# GPO_IF.net
KiCad netlist of a schematic drawn in Altium Designer
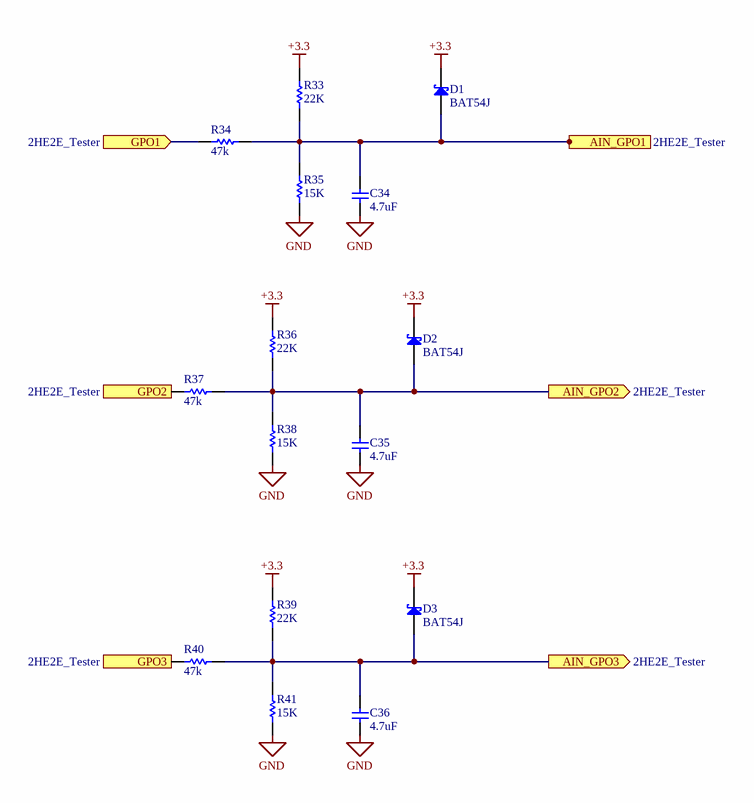
[diagram p0: GPO_IF.SchDoc]

(export (version "E")
  (design (tool "Eeschema 10.0.6"))
  (components
    (comp (ref "C34")
      (value "4.7uF")
      (footprint "0603M-C")
      (description "Ceramic Capacitor")
      (fields (field (name "Comment") "Cap Ceramic"))
      (libsource (lib "Plume") (part "Cap Ceramic"))
    )
    (comp (ref "C35")
      (value "4.7uF")
      (footprint "0603M-C")
      (description "Ceramic Capacitor")
      (fields (field (name "Comment") "Cap Ceramic"))
      (libsource (lib "Plume") (part "Cap Ceramic"))
    )
    (comp (ref "C36")
      (value "4.7uF")
      (footprint "0603M-C")
      (description "Ceramic Capacitor")
      (fields (field (name "Comment") "Cap Ceramic"))
      (libsource (lib "Plume") (part "Cap Ceramic"))
    )
    (comp (ref "D1")
      (value "BAT54J")
      (footprint "SOD323")
      (description "Diodo Schottky")
      (libsource (lib "Plume") (part "Diodo Schottky"))
    )
    (comp (ref "D2")
      (value "BAT54J")
      (footprint "SOD323")
      (description "Diodo Schottky")
      (libsource (lib "Plume") (part "Diodo Schottky"))
    )
    (comp (ref "D3")
      (value "BAT54J")
      (footprint "SOD323")
      (description "Diodo Schottky")
      (libsource (lib "Plume") (part "Diodo Schottky"))
    )
    (comp (ref "R33")
      (value "22K")
      (footprint "0603M")
      (description "Resistor")
      (libsource (lib "Plume") (part "Resistor"))
    )
    (comp (ref "R34")
      (value "47k")
      (footprint "0603M")
      (description "Resistor")
      (libsource (lib "Plume") (part "Resistor"))
    )
    (comp (ref "R35")
      (value "15K")
      (footprint "0603M")
      (description "Resistor")
      (libsource (lib "Plume") (part "Resistor"))
    )
    (comp (ref "R36")
      (value "22K")
      (footprint "0603M")
      (description "Resistor")
      (libsource (lib "Plume") (part "Resistor"))
    )
    (comp (ref "R37")
      (value "47k")
      (footprint "0603M")
      (description "Resistor")
      (libsource (lib "Plume") (part "Resistor"))
    )
    (comp (ref "R38")
      (value "15K")
      (footprint "0603M")
      (description "Resistor")
      (libsource (lib "Plume") (part "Resistor"))
    )
    (comp (ref "R39")
      (value "22K")
      (footprint "0603M")
      (description "Resistor")
      (libsource (lib "Plume") (part "Resistor"))
    )
    (comp (ref "R40")
      (value "47k")
      (footprint "0603M")
      (description "Resistor")
      (libsource (lib "Plume") (part "Resistor"))
    )
    (comp (ref "R41")
      (value "15K")
      (footprint "0603M")
      (description "Resistor")
      (libsource (lib "Plume") (part "Resistor"))
    )
  )
  (nets
    (net (code "1") (name "+3.3") (class "Default")
      (node (ref "D1") (pin "2") (pinfunction "K_2") (pintype "passive"))
      (node (ref "D2") (pin "2") (pinfunction "K_2") (pintype "passive"))
      (node (ref "D3") (pin "2") (pinfunction "K_2") (pintype "passive"))
      (node (ref "R33") (pin "2") (pinfunction "2_2") (pintype "passive"))
      (node (ref "R36") (pin "2") (pinfunction "2_2") (pintype "passive"))
      (node (ref "R39") (pin "2") (pinfunction "2_2") (pintype "passive"))
    )
    (net (code "2") (name "/AIN_GPO1") (class "Default")
      (node (ref "C34") (pin "2") (pinfunction "2_2") (pintype "passive"))
      (node (ref "D1") (pin "1") (pinfunction "A_1") (pintype "passive"))
      (node (ref "R33") (pin "1") (pinfunction "1_1") (pintype "passive"))
      (node (ref "R34") (pin "2") (pinfunction "2_2") (pintype "passive"))
      (node (ref "R35") (pin "2") (pinfunction "2_2") (pintype "passive"))
    )
    (net (code "3") (name "/AIN_GPO2") (class "Default")
      (node (ref "C35") (pin "2") (pinfunction "2_2") (pintype "passive"))
      (node (ref "D2") (pin "1") (pinfunction "A_1") (pintype "passive"))
      (node (ref "R36") (pin "1") (pinfunction "1_1") (pintype "passive"))
      (node (ref "R37") (pin "2") (pinfunction "2_2") (pintype "passive"))
      (node (ref "R38") (pin "2") (pinfunction "2_2") (pintype "passive"))
    )
    (net (code "4") (name "/AIN_GPO3") (class "Default")
      (node (ref "C36") (pin "2") (pinfunction "2_2") (pintype "passive"))
      (node (ref "D3") (pin "1") (pinfunction "A_1") (pintype "passive"))
      (node (ref "R39") (pin "1") (pinfunction "1_1") (pintype "passive"))
      (node (ref "R40") (pin "2") (pinfunction "2_2") (pintype "passive"))
      (node (ref "R41") (pin "2") (pinfunction "2_2") (pintype "passive"))
    )
    (net (code "5") (name "/GPO1") (class "Default")
      (node (ref "R34") (pin "1") (pinfunction "1_1") (pintype "passive"))
    )
    (net (code "6") (name "/GPO2") (class "Default")
      (node (ref "R37") (pin "1") (pinfunction "1_1") (pintype "passive"))
    )
    (net (code "7") (name "/GPO3") (class "Default")
      (node (ref "R40") (pin "1") (pinfunction "1_1") (pintype "passive"))
    )
    (net (code "8") (name "GND") (class "Default")
      (node (ref "C34") (pin "1") (pinfunction "1_1") (pintype "passive"))
      (node (ref "C35") (pin "1") (pinfunction "1_1") (pintype "passive"))
      (node (ref "C36") (pin "1") (pinfunction "1_1") (pintype "passive"))
      (node (ref "R35") (pin "1") (pinfunction "1_1") (pintype "passive"))
      (node (ref "R38") (pin "1") (pinfunction "1_1") (pintype "passive"))
      (node (ref "R41") (pin "1") (pinfunction "1_1") (pintype "passive"))
    )
  )
)
